# Cool.net
KiCad netlist of a schematic drawn in EAGLE
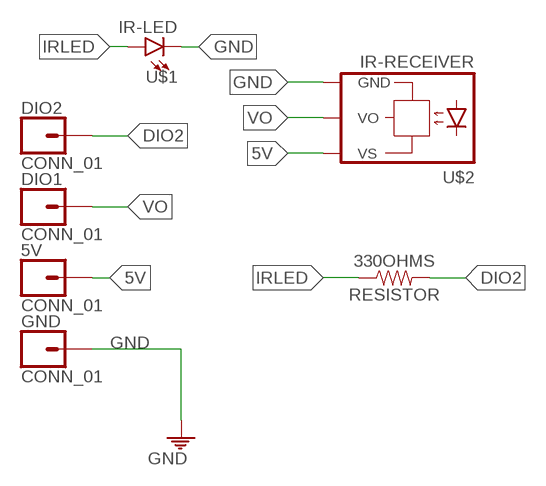
[diagram p0: schematic, sheet 1]

(export (version "E")
  (design (tool "Eeschema 10.0.6"))
  (components
    (comp (ref "5V")
      (value "CONN_01")
      (footprint "eagle-import:1X01")
      (libsource (lib "eagle-import") (part "CONN_01"))
    )
    (comp (ref "330OHMS")
      (value "RESISTOR")
      (footprint "eagle-import:AXIAL-0.3")
      (libsource (lib "eagle-import") (part "RESISTOR"))
    )
    (comp (ref "DIO1")
      (value "CONN_01")
      (footprint "eagle-import:1X01")
      (libsource (lib "eagle-import") (part "CONN_01"))
    )
    (comp (ref "DIO2")
      (value "CONN_01")
      (footprint "eagle-import:1X01")
      (libsource (lib "eagle-import") (part "CONN_01"))
    )
    (comp (ref "GND")
      (value "CONN_01")
      (footprint "eagle-import:1X01")
      (libsource (lib "eagle-import") (part "CONN_01"))
    )
    (comp (ref "U$1")
      (value "IR-LED")
      (footprint "eagle-import:LED_5MM")
      (libsource (lib "eagle-import") (part "IR-LED"))
    )
    (comp (ref "U$2")
      (value "IR-RECEIVER")
      (footprint "eagle-import:TSOP17_TB1")
      (libsource (lib "eagle-import") (part "IR-RECEIVER"))
    )
  )
  (nets
    (net (code "1") (name "5V") (class "Default")
      (node (ref "5V") (pin "1") (pinfunction "1_1") (pintype "passive"))
      (node (ref "U$2") (pin "VS") (pinfunction "VS_VS") (pintype "bidirectional"))
    )
    (net (code "2") (name "DIO2") (class "Default")
      (node (ref "330OHMS") (pin "P$2") (pinfunction "2_P$2") (pintype "passive"))
      (node (ref "DIO2") (pin "1") (pinfunction "1_1") (pintype "passive"))
    )
    (net (code "3") (name "GND") (class "Default")
      (node (ref "GND") (pin "1") (pinfunction "1_1") (pintype "passive"))
      (node (ref "U$1") (pin "K") (pinfunction "C_K") (pintype "passive"))
      (node (ref "U$2") (pin "GND") (pinfunction "GND_GND") (pintype "bidirectional"))
    )
    (net (code "4") (name "IRLED") (class "Default")
      (node (ref "330OHMS") (pin "P$1") (pinfunction "1_P$1") (pintype "passive"))
      (node (ref "U$1") (pin "A") (pinfunction "A_A") (pintype "passive"))
    )
    (net (code "5") (name "VO") (class "Default")
      (node (ref "DIO1") (pin "1") (pinfunction "1_1") (pintype "passive"))
      (node (ref "U$2") (pin "VO") (pinfunction "VO_VO") (pintype "open_collector"))
    )
  )
)
